# Sch_stm32f103c8.net
KiCad netlist of a schematic drawn in Altium Designer
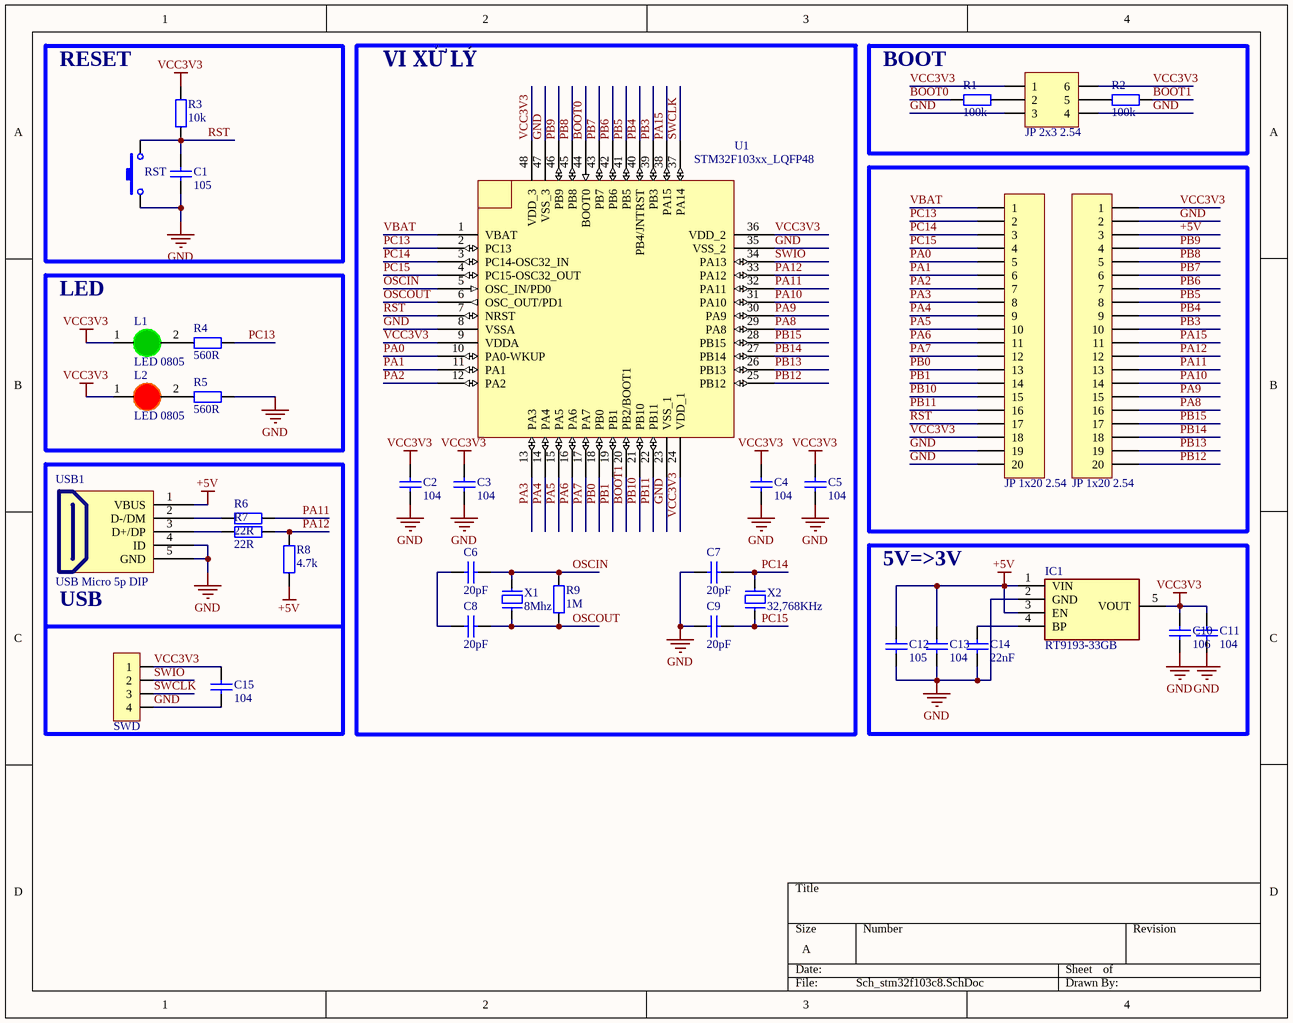
[diagram p0: Sch_stm32f103c8.SchDoc]

(export (version "E")
  (design (tool "Eeschema 10.0.6"))
  (components
    (comp (ref "C1")
      (value "105")
      (footprint "tu 0805")
      (description "Dán")
      (libsource (lib "Tu dien") (part "Tu 0805 105 50V 10%"))
    )
    (comp (ref "C2")
      (value "104")
      (footprint "tu 0805")
      (description "Dán")
      (libsource (lib "Tu dien") (part "Tu 0805 104 50V 10%"))
    )
    (comp (ref "C3")
      (value "104")
      (footprint "tu 0805")
      (description "Dán")
      (libsource (lib "Tu dien") (part "Tu 0805 104 50V 10%"))
    )
    (comp (ref "C4")
      (value "104")
      (footprint "tu 0805")
      (description "Dán")
      (libsource (lib "Tu dien") (part "Tu 0805 104 50V 10%"))
    )
    (comp (ref "C5")
      (value "104")
      (footprint "tu 0805")
      (description "Dán")
      (libsource (lib "Tu dien") (part "Tu 0805 104 50V 10%"))
    )
    (comp (ref "C6")
      (value "20pF")
      (footprint "tu 0805")
      (description "Dán")
      (libsource (lib "Tu dien") (part "Tu 0805 20pF 50V 10%"))
    )
    (comp (ref "C7")
      (value "20pF")
      (footprint "tu 0805")
      (description "Dán")
      (libsource (lib "Tu dien") (part "Tu 0805 20pF 50V 10%"))
    )
    (comp (ref "C8")
      (value "20pF")
      (footprint "tu 0805")
      (description "Dán")
      (libsource (lib "Tu dien") (part "Tu 0805 20pF 50V 10%"))
    )
    (comp (ref "C9")
      (value "20pF")
      (footprint "tu 0805")
      (description "Dán")
      (libsource (lib "Tu dien") (part "Tu 0805 20pF 50V 10%"))
    )
    (comp (ref "C10")
      (value "106")
      (footprint "tu 0805")
      (description "Dán")
      (libsource (lib "Tu dien") (part "Tu 0805 106 16V 10%"))
    )
    (comp (ref "C11")
      (value "104")
      (footprint "tu 0805")
      (description "Dán")
      (libsource (lib "Tu dien") (part "Tu 0805 104 50V 10%"))
    )
    (comp (ref "C12")
      (value "105")
      (footprint "tu 0805")
      (description "Dán")
      (libsource (lib "Tu dien") (part "Tu 0805 105 50V 10%"))
    )
    (comp (ref "C13")
      (value "104")
      (footprint "tu 0805")
      (description "Dán")
      (libsource (lib "Tu dien") (part "Tu 0805 104 50V 10%"))
    )
    (comp (ref "C14")
      (value "22nF")
      (footprint "tu 0805")
      (description "Dán")
      (libsource (lib "Tu dien") (part "Tu 0805 22nF 50V 20%"))
    )
    (comp (ref "C15")
      (value "104")
      (footprint "tu 0805")
      (description "Dán")
      (libsource (lib "Tu dien") (part "Tu 0805 104 50V 10%"))
    )
    (comp (ref "IC1")
      (value "RT9193-33GB")
      (footprint "SamacSys:SOT94P279X130-5N")
      (description "Integrated Circuit")
      (libsource (lib "test") (part "RT9193-33GB"))
    )
    (comp (ref "JP1")
      (value "JP 2x3 2.54")
      (footprint "JP 2x3 DT")
      (description "Cắm")
      (libsource (lib "Jump") (part "JP 2x3 2.54 Duc Thang"))
    )
    (comp (ref "JP2")
      (value "JP 1x20 2.54")
      (footprint "JP 1x20 DT")
      (description "Cắm")
      (libsource (lib "Jump") (part "JP 1x20 2.54 Duc Thang"))
    )
    (comp (ref "JP3")
      (value "JP 1x20 2.54")
      (footprint "JP 1x20 DT")
      (description "Cắm")
      (libsource (lib "") (part "JP 1x20 2.54 Duc Thang_1"))
    )
    (comp (ref "JP4")
      (value "SWD")
      (footprint "JP 1x4 DT")
      (description "Cắm")
      (libsource (lib "Jump") (part "JP 1x4 2.54 Duc Thang"))
    )
    (comp (ref "L1")
      (value "LED 0805")
      (footprint "LED-0805-Green")
      (description "Dán")
      (libsource (lib "Led") (part "LED 0805 Xanh La"))
    )
    (comp (ref "L2")
      (value "LED 0805")
      (footprint "LED-0805-Red")
      (description "Dán")
      (libsource (lib "Led") (part "LED 0805 Do"))
    )
    (comp (ref "R1")
      (value "100k")
      (footprint "tro smd 0805")
      (description "Dán")
      (libsource (lib "Dien Tro") (part "Tro 0805 5% 100k"))
    )
    (comp (ref "R2")
      (value "100k")
      (footprint "tro smd 0805")
      (description "Dán")
      (libsource (lib "Dien Tro") (part "Tro 0805 5% 100k"))
    )
    (comp (ref "R3")
      (value "10k")
      (footprint "tro smd 0805")
      (description "Dán")
      (libsource (lib "Dien Tro") (part "Tro 0805 5% 10k"))
    )
    (comp (ref "R4")
      (value "560R")
      (footprint "tro smd 0805")
      (description "Dán")
      (libsource (lib "Dien Tro") (part "Tro 0805 5% 560R"))
    )
    (comp (ref "R5")
      (value "560R")
      (footprint "tro smd 0805")
      (description "Dán")
      (libsource (lib "Dien Tro") (part "Tro 0805 5% 560R"))
    )
    (comp (ref "R6")
      (value "22R")
      (footprint "tro smd 0805")
      (description "Dán")
      (libsource (lib "Dien Tro") (part "Tro 0805 5% 22R"))
    )
    (comp (ref "R7")
      (value "22R")
      (footprint "tro smd 0805")
      (description "Dán")
      (libsource (lib "Dien Tro") (part "Tro 0805 5% 22R"))
    )
    (comp (ref "R8")
      (value "4.7k")
      (footprint "tro smd 0805")
      (description "Dán")
      (libsource (lib "Dien Tro") (part "Tro 0805 5% 4.7k"))
    )
    (comp (ref "R9")
      (value "1M")
      (footprint "tro smd 0603")
      (description "Dán")
      (libsource (lib "Dien Tro") (part "Tro 0603 5% 1M"))
    )
    (comp (ref "RST")
      (value "Nut Nhan 2 Chan SMD 3x6x2.5")
      (footprint "Nut Nhan 2 Chan SMD 3x6x2.5")
      (libsource (lib "Component") (part "Nut Nhan 2 Chan SMD 3x6x2.5"))
    )
    (comp (ref "U1")
      (value "STM32F103xx_LQFP48")
      (footprint "STM32_LQPF48")
      (fields (field (name "PUBLISHER") "Altium Limited"))
      (libsource (lib "IC") (part "STM32F103xx_LQFP48"))
    )
    (comp (ref "USB1")
      (value "USB Micro 5p DIP")
      (footprint "USB Micro 5p DIP")
      (description "USB Type B")
      (libsource (lib "Component") (part "USB Micro 5p DIP"))
    )
    (comp (ref "X1")
      (value "8Mhz")
      (footprint "XT2")
      (description "Crystal, 32.768 KHz, -40 to 85 degC, 3.2 x 1.5 x 0.9 mm SMD")
      (libsource (lib "TechMT.VN_Lib_Project v2") (part "XT2"))
    )
    (comp (ref "X2")
      (value "32,768KHz")
      (footprint "XT2-32.768KHz-2_V")
      (description "Crystal, 32.768 KHz, -40 to 85 degC, 3.2 x 1.5 x 0.9 mm SMD")
      (libsource (lib "TechMT.VN_Lib_Project v2") (part "XT2"))
    )
  )
  (nets
    (net (code "1") (name "+5V") (class "Default")
      (node (ref "C12") (pin "1") (pinfunction "1_1") (pintype "passive"))
      (node (ref "C13") (pin "1") (pinfunction "1_1") (pintype "passive"))
      (node (ref "IC1") (pin "1") (pinfunction "VIN_1") (pintype "passive"))
      (node (ref "IC1") (pin "3") (pinfunction "EN_3") (pintype "passive"))
      (node (ref "JP3") (pin "3") (pinfunction "3_3") (pintype "passive"))
      (node (ref "R8") (pin "1") (pinfunction "1_1") (pintype "passive"))
      (node (ref "USB1") (pin "1") (pinfunction "VBUS_1") (pintype "passive"))
    )
    (net (code "2") (name "/BOOT0") (class "Default")
      (node (ref "R1") (pin "1") (pinfunction "1_1") (pintype "passive"))
      (node (ref "U1") (pin "44") (pinfunction "BOOT0_44") (pintype "input"))
    )
    (net (code "3") (name "/BOOT1") (class "Default")
      (node (ref "R2") (pin "2") (pinfunction "2_2") (pintype "passive"))
      (node (ref "U1") (pin "20") (pinfunction "PB2/BOOT1_20") (pintype "bidirectional"))
    )
    (net (code "4") (name "/OSCIN") (class "Default")
      (node (ref "C6") (pin "1") (pinfunction "1_1") (pintype "passive"))
      (node (ref "R9") (pin "2") (pinfunction "2_2") (pintype "passive"))
      (node (ref "U1") (pin "5") (pinfunction "OSC_IN/PD0_5") (pintype "input"))
      (node (ref "X1") (pin "2") (pinfunction "2_2") (pintype "passive"))
    )
    (net (code "5") (name "/OSCOUT") (class "Default")
      (node (ref "C8") (pin "1") (pinfunction "1_1") (pintype "passive"))
      (node (ref "R9") (pin "1") (pinfunction "1_1") (pintype "passive"))
      (node (ref "U1") (pin "6") (pinfunction "OSC_OUT/PD1_6") (pintype "output"))
      (node (ref "X1") (pin "1") (pinfunction "1_1") (pintype "passive"))
    )
    (net (code "6") (name "/PA0") (class "Default")
      (node (ref "JP2") (pin "5") (pinfunction "5_5") (pintype "passive"))
      (node (ref "U1") (pin "10") (pinfunction "PA0-WKUP_10") (pintype "bidirectional"))
    )
    (net (code "7") (name "/PA1") (class "Default")
      (node (ref "JP2") (pin "6") (pinfunction "6_6") (pintype "passive"))
      (node (ref "U1") (pin "11") (pinfunction "PA1_11") (pintype "bidirectional"))
    )
    (net (code "8") (name "/PA2") (class "Default")
      (node (ref "JP2") (pin "7") (pinfunction "7_7") (pintype "passive"))
      (node (ref "U1") (pin "12") (pinfunction "PA2_12") (pintype "bidirectional"))
    )
    (net (code "9") (name "/PA3") (class "Default")
      (node (ref "JP2") (pin "8") (pinfunction "8_8") (pintype "passive"))
      (node (ref "U1") (pin "13") (pinfunction "PA3_13") (pintype "bidirectional"))
    )
    (net (code "10") (name "/PA4") (class "Default")
      (node (ref "JP2") (pin "9") (pinfunction "9_9") (pintype "passive"))
      (node (ref "U1") (pin "14") (pinfunction "PA4_14") (pintype "bidirectional"))
    )
    (net (code "11") (name "/PA5") (class "Default")
      (node (ref "JP2") (pin "10") (pinfunction "10_10") (pintype "passive"))
      (node (ref "U1") (pin "15") (pinfunction "PA5_15") (pintype "bidirectional"))
    )
    (net (code "12") (name "/PA6") (class "Default")
      (node (ref "JP2") (pin "11") (pinfunction "11_11") (pintype "passive"))
      (node (ref "U1") (pin "16") (pinfunction "PA6_16") (pintype "bidirectional"))
    )
    (net (code "13") (name "/PA7") (class "Default")
      (node (ref "JP2") (pin "12") (pinfunction "12_12") (pintype "passive"))
      (node (ref "U1") (pin "17") (pinfunction "PA7_17") (pintype "bidirectional"))
    )
    (net (code "14") (name "/PA8") (class "Default")
      (node (ref "JP3") (pin "16") (pinfunction "16_16") (pintype "passive"))
      (node (ref "U1") (pin "29") (pinfunction "PA8_29") (pintype "bidirectional"))
    )
    (net (code "15") (name "/PA9") (class "Default")
      (node (ref "JP3") (pin "15") (pinfunction "15_15") (pintype "passive"))
      (node (ref "U1") (pin "30") (pinfunction "PA9_30") (pintype "bidirectional"))
    )
    (net (code "16") (name "/PA10") (class "Default")
      (node (ref "JP3") (pin "14") (pinfunction "14_14") (pintype "passive"))
      (node (ref "U1") (pin "31") (pinfunction "PA10_31") (pintype "bidirectional"))
    )
    (net (code "17") (name "/PA11") (class "Default")
      (node (ref "JP3") (pin "13") (pinfunction "13_13") (pintype "passive"))
      (node (ref "R6") (pin "2") (pinfunction "2_2") (pintype "passive"))
      (node (ref "U1") (pin "32") (pinfunction "PA11_32") (pintype "bidirectional"))
    )
    (net (code "18") (name "/PA12") (class "Default")
      (node (ref "JP3") (pin "12") (pinfunction "12_12") (pintype "passive"))
      (node (ref "R7") (pin "2") (pinfunction "2_2") (pintype "passive"))
      (node (ref "R8") (pin "2") (pinfunction "2_2") (pintype "passive"))
      (node (ref "U1") (pin "33") (pinfunction "PA12_33") (pintype "bidirectional"))
    )
    (net (code "19") (name "/PA15") (class "Default")
      (node (ref "JP3") (pin "11") (pinfunction "11_11") (pintype "passive"))
      (node (ref "U1") (pin "38") (pinfunction "PA15_38") (pintype "bidirectional"))
    )
    (net (code "20") (name "/PB0") (class "Default")
      (node (ref "JP2") (pin "13") (pinfunction "13_13") (pintype "passive"))
      (node (ref "U1") (pin "18") (pinfunction "PB0_18") (pintype "bidirectional"))
    )
    (net (code "21") (name "/PB1") (class "Default")
      (node (ref "JP2") (pin "14") (pinfunction "14_14") (pintype "passive"))
      (node (ref "U1") (pin "19") (pinfunction "PB1_19") (pintype "bidirectional"))
    )
    (net (code "22") (name "/PB3") (class "Default")
      (node (ref "JP3") (pin "10") (pinfunction "10_10") (pintype "passive"))
      (node (ref "U1") (pin "39") (pinfunction "PB3_39") (pintype "bidirectional"))
    )
    (net (code "23") (name "/PB4") (class "Default")
      (node (ref "JP3") (pin "9") (pinfunction "9_9") (pintype "passive"))
      (node (ref "U1") (pin "40") (pinfunction "PB4/JNTRST_40") (pintype "bidirectional"))
    )
    (net (code "24") (name "/PB5") (class "Default")
      (node (ref "JP3") (pin "8") (pinfunction "8_8") (pintype "passive"))
      (node (ref "U1") (pin "41") (pinfunction "PB5_41") (pintype "bidirectional"))
    )
    (net (code "25") (name "/PB6") (class "Default")
      (node (ref "JP3") (pin "7") (pinfunction "7_7") (pintype "passive"))
      (node (ref "U1") (pin "42") (pinfunction "PB6_42") (pintype "bidirectional"))
    )
    (net (code "26") (name "/PB7") (class "Default")
      (node (ref "JP3") (pin "6") (pinfunction "6_6") (pintype "passive"))
      (node (ref "U1") (pin "43") (pinfunction "PB7_43") (pintype "bidirectional"))
    )
    (net (code "27") (name "/PB8") (class "Default")
      (node (ref "JP3") (pin "5") (pinfunction "5_5") (pintype "passive"))
      (node (ref "U1") (pin "45") (pinfunction "PB8_45") (pintype "bidirectional"))
    )
    (net (code "28") (name "/PB9") (class "Default")
      (node (ref "JP3") (pin "4") (pinfunction "4_4") (pintype "passive"))
      (node (ref "U1") (pin "46") (pinfunction "PB9_46") (pintype "bidirectional"))
    )
    (net (code "29") (name "/PB10") (class "Default")
      (node (ref "JP2") (pin "15") (pinfunction "15_15") (pintype "passive"))
      (node (ref "U1") (pin "21") (pinfunction "PB10_21") (pintype "bidirectional"))
    )
    (net (code "30") (name "/PB11") (class "Default")
      (node (ref "JP2") (pin "16") (pinfunction "16_16") (pintype "passive"))
      (node (ref "U1") (pin "22") (pinfunction "PB11_22") (pintype "bidirectional"))
    )
    (net (code "31") (name "/PB12") (class "Default")
      (node (ref "JP3") (pin "20") (pinfunction "20_20") (pintype "passive"))
      (node (ref "U1") (pin "25") (pinfunction "PB12_25") (pintype "bidirectional"))
    )
    (net (code "32") (name "/PB13") (class "Default")
      (node (ref "JP3") (pin "19") (pinfunction "19_19") (pintype "passive"))
      (node (ref "U1") (pin "26") (pinfunction "PB13_26") (pintype "bidirectional"))
    )
    (net (code "33") (name "/PB14") (class "Default")
      (node (ref "JP3") (pin "18") (pinfunction "18_18") (pintype "passive"))
      (node (ref "U1") (pin "27") (pinfunction "PB14_27") (pintype "bidirectional"))
    )
    (net (code "34") (name "/PB15") (class "Default")
      (node (ref "JP3") (pin "17") (pinfunction "17_17") (pintype "passive"))
      (node (ref "U1") (pin "28") (pinfunction "PB15_28") (pintype "bidirectional"))
    )
    (net (code "35") (name "/PC13") (class "Default")
      (node (ref "JP2") (pin "2") (pinfunction "2_2") (pintype "passive"))
      (node (ref "R4") (pin "2") (pinfunction "2_2") (pintype "passive"))
      (node (ref "U1") (pin "2") (pinfunction "PC13_2") (pintype "bidirectional"))
    )
    (net (code "36") (name "/PC14") (class "Default")
      (node (ref "C7") (pin "1") (pinfunction "1_1") (pintype "passive"))
      (node (ref "JP2") (pin "3") (pinfunction "3_3") (pintype "passive"))
      (node (ref "U1") (pin "3") (pinfunction "PC14-OSC32_IN_3") (pintype "bidirectional"))
      (node (ref "X2") (pin "2") (pinfunction "2_2") (pintype "passive"))
    )
    (net (code "37") (name "/PC15") (class "Default")
      (node (ref "C9") (pin "1") (pinfunction "1_1") (pintype "passive"))
      (node (ref "JP2") (pin "4") (pinfunction "4_4") (pintype "passive"))
      (node (ref "U1") (pin "4") (pinfunction "PC15-OSC32_OUT_4") (pintype "bidirectional"))
      (node (ref "X2") (pin "1") (pinfunction "1_1") (pintype "passive"))
    )
    (net (code "38") (name "/RST") (class "Default")
      (node (ref "C1") (pin "1") (pinfunction "1_1") (pintype "passive"))
      (node (ref "JP2") (pin "17") (pinfunction "17_17") (pintype "passive"))
      (node (ref "R3") (pin "1") (pinfunction "1_1") (pintype "passive"))
      (node (ref "RST") (pin "2") (pinfunction "2_2") (pintype "passive"))
      (node (ref "U1") (pin "7") (pinfunction "NRST_7") (pintype "bidirectional"))
    )
    (net (code "39") (name "/SWCLK") (class "Default")
      (node (ref "JP4") (pin "3") (pinfunction "3_3") (pintype "passive"))
      (node (ref "U1") (pin "37") (pinfunction "PA14_37") (pintype "bidirectional"))
    )
    (net (code "40") (name "/SWIO") (class "Default")
      (node (ref "JP4") (pin "2") (pinfunction "2_2") (pintype "passive"))
      (node (ref "U1") (pin "34") (pinfunction "PA13_34") (pintype "bidirectional"))
    )
    (net (code "41") (name "/VBAT") (class "Default")
      (node (ref "JP2") (pin "1") (pinfunction "1_1") (pintype "passive"))
      (node (ref "U1") (pin "1") (pinfunction "VBAT_1") (pintype "power_in"))
    )
    (net (code "42") (name "GND") (class "Default")
      (node (ref "C1") (pin "2") (pinfunction "2_2") (pintype "passive"))
      (node (ref "C10") (pin "2") (pinfunction "2_2") (pintype "passive"))
      (node (ref "C11") (pin "2") (pinfunction "2_2") (pintype "passive"))
      (node (ref "C12") (pin "2") (pinfunction "2_2") (pintype "passive"))
      (node (ref "C13") (pin "2") (pinfunction "2_2") (pintype "passive"))
      (node (ref "C14") (pin "2") (pinfunction "2_2") (pintype "passive"))
      (node (ref "C15") (pin "2") (pinfunction "2_2") (pintype "passive"))
      (node (ref "C2") (pin "2") (pinfunction "2_2") (pintype "passive"))
      (node (ref "C3") (pin "2") (pinfunction "2_2") (pintype "passive"))
      (node (ref "C4") (pin "2") (pinfunction "2_2") (pintype "passive"))
      (node (ref "C5") (pin "2") (pinfunction "2_2") (pintype "passive"))
      (node (ref "C7") (pin "2") (pinfunction "2_2") (pintype "passive"))
      (node (ref "C9") (pin "2") (pinfunction "2_2") (pintype "passive"))
      (node (ref "IC1") (pin "2") (pinfunction "GND_2") (pintype "passive"))
      (node (ref "JP1") (pin "3") (pinfunction "3_3") (pintype "passive"))
      (node (ref "JP1") (pin "4") (pinfunction "4_4") (pintype "passive"))
      (node (ref "JP2") (pin "19") (pinfunction "19_19") (pintype "passive"))
      (node (ref "JP2") (pin "20") (pinfunction "20_20") (pintype "passive"))
      (node (ref "JP3") (pin "2") (pinfunction "2_2") (pintype "passive"))
      (node (ref "JP4") (pin "4") (pinfunction "4_4") (pintype "passive"))
      (node (ref "R5") (pin "2") (pinfunction "2_2") (pintype "passive"))
      (node (ref "RST") (pin "1") (pinfunction "1_1") (pintype "passive"))
      (node (ref "U1") (pin "23") (pinfunction "VSS_1_23") (pintype "power_in"))
      (node (ref "U1") (pin "35") (pinfunction "VSS_2_35") (pintype "power_in"))
      (node (ref "U1") (pin "47") (pinfunction "VSS_3_47") (pintype "power_in"))
      (node (ref "U1") (pin "8") (pinfunction "VSSA_8") (pintype "power_in"))
      (node (ref "USB1") (pin "4") (pinfunction "ID_4") (pintype "passive"))
      (node (ref "USB1") (pin "5") (pinfunction "GND_5") (pintype "passive"))
    )
    (net (code "43") (name "Net-(C6-Pad2)") (class "Default")
      (node (ref "C6") (pin "2") (pinfunction "2_2") (pintype "passive"))
      (node (ref "C8") (pin "2") (pinfunction "2_2") (pintype "passive"))
    )
    (net (code "44") (name "Net-(IC1-BP)") (class "Default")
      (node (ref "C14") (pin "1") (pinfunction "1_1") (pintype "passive"))
      (node (ref "IC1") (pin "4") (pinfunction "BP_4") (pintype "passive"))
    )
    (net (code "45") (name "Net-(JP1-Pad2)") (class "Default")
      (node (ref "JP1") (pin "2") (pinfunction "2_2") (pintype "passive"))
      (node (ref "R1") (pin "2") (pinfunction "2_2") (pintype "passive"))
    )
    (net (code "46") (name "Net-(JP1-Pad5)") (class "Default")
      (node (ref "JP1") (pin "5") (pinfunction "5_5") (pintype "passive"))
      (node (ref "R2") (pin "1") (pinfunction "1_1") (pintype "passive"))
    )
    (net (code "47") (name "Net-(L1-K)") (class "Default")
      (node (ref "L1") (pin "2") (pinfunction "K_2") (pintype "passive"))
      (node (ref "R4") (pin "1") (pinfunction "1_1") (pintype "passive"))
    )
    (net (code "48") (name "Net-(L2-K)") (class "Default")
      (node (ref "L2") (pin "2") (pinfunction "K_2") (pintype "passive"))
      (node (ref "R5") (pin "1") (pinfunction "1_1") (pintype "passive"))
    )
    (net (code "49") (name "Net-(USB1-D+{slash}DP)") (class "Default")
      (node (ref "R7") (pin "1") (pinfunction "1_1") (pintype "passive"))
      (node (ref "USB1") (pin "3") (pinfunction "D+/DP_3") (pintype "passive"))
    )
    (net (code "50") (name "Net-(USB1-D-{slash}DM)") (class "Default")
      (node (ref "R6") (pin "1") (pinfunction "1_1") (pintype "passive"))
      (node (ref "USB1") (pin "2") (pinfunction "D-/DM_2") (pintype "passive"))
    )
    (net (code "51") (name "VCC3V3") (class "Default")
      (node (ref "C10") (pin "1") (pinfunction "1_1") (pintype "passive"))
      (node (ref "C11") (pin "1") (pinfunction "1_1") (pintype "passive"))
      (node (ref "C15") (pin "1") (pinfunction "1_1") (pintype "passive"))
      (node (ref "C2") (pin "1") (pinfunction "1_1") (pintype "passive"))
      (node (ref "C3") (pin "1") (pinfunction "1_1") (pintype "passive"))
      (node (ref "C4") (pin "1") (pinfunction "1_1") (pintype "passive"))
      (node (ref "C5") (pin "1") (pinfunction "1_1") (pintype "passive"))
      (node (ref "IC1") (pin "5") (pinfunction "VOUT_5") (pintype "passive"))
      (node (ref "JP1") (pin "1") (pinfunction "1_1") (pintype "passive"))
      (node (ref "JP1") (pin "6") (pinfunction "6_6") (pintype "passive"))
      (node (ref "JP2") (pin "18") (pinfunction "18_18") (pintype "passive"))
      (node (ref "JP3") (pin "1") (pinfunction "1_1") (pintype "passive"))
      (node (ref "JP4") (pin "1") (pinfunction "1_1") (pintype "passive"))
      (node (ref "L1") (pin "1") (pinfunction "A_1") (pintype "passive"))
      (node (ref "L2") (pin "1") (pinfunction "A_1") (pintype "passive"))
      (node (ref "R3") (pin "2") (pinfunction "2_2") (pintype "passive"))
      (node (ref "U1") (pin "24") (pinfunction "VDD_1_24") (pintype "power_in"))
      (node (ref "U1") (pin "36") (pinfunction "VDD_2_36") (pintype "power_in"))
      (node (ref "U1") (pin "48") (pinfunction "VDD_3_48") (pintype "power_in"))
      (node (ref "U1") (pin "9") (pinfunction "VDDA_9") (pintype "power_in"))
    )
  )
)
